# NB-Fi-Router.net
KiCad netlist of a schematic drawn in Altium Designer
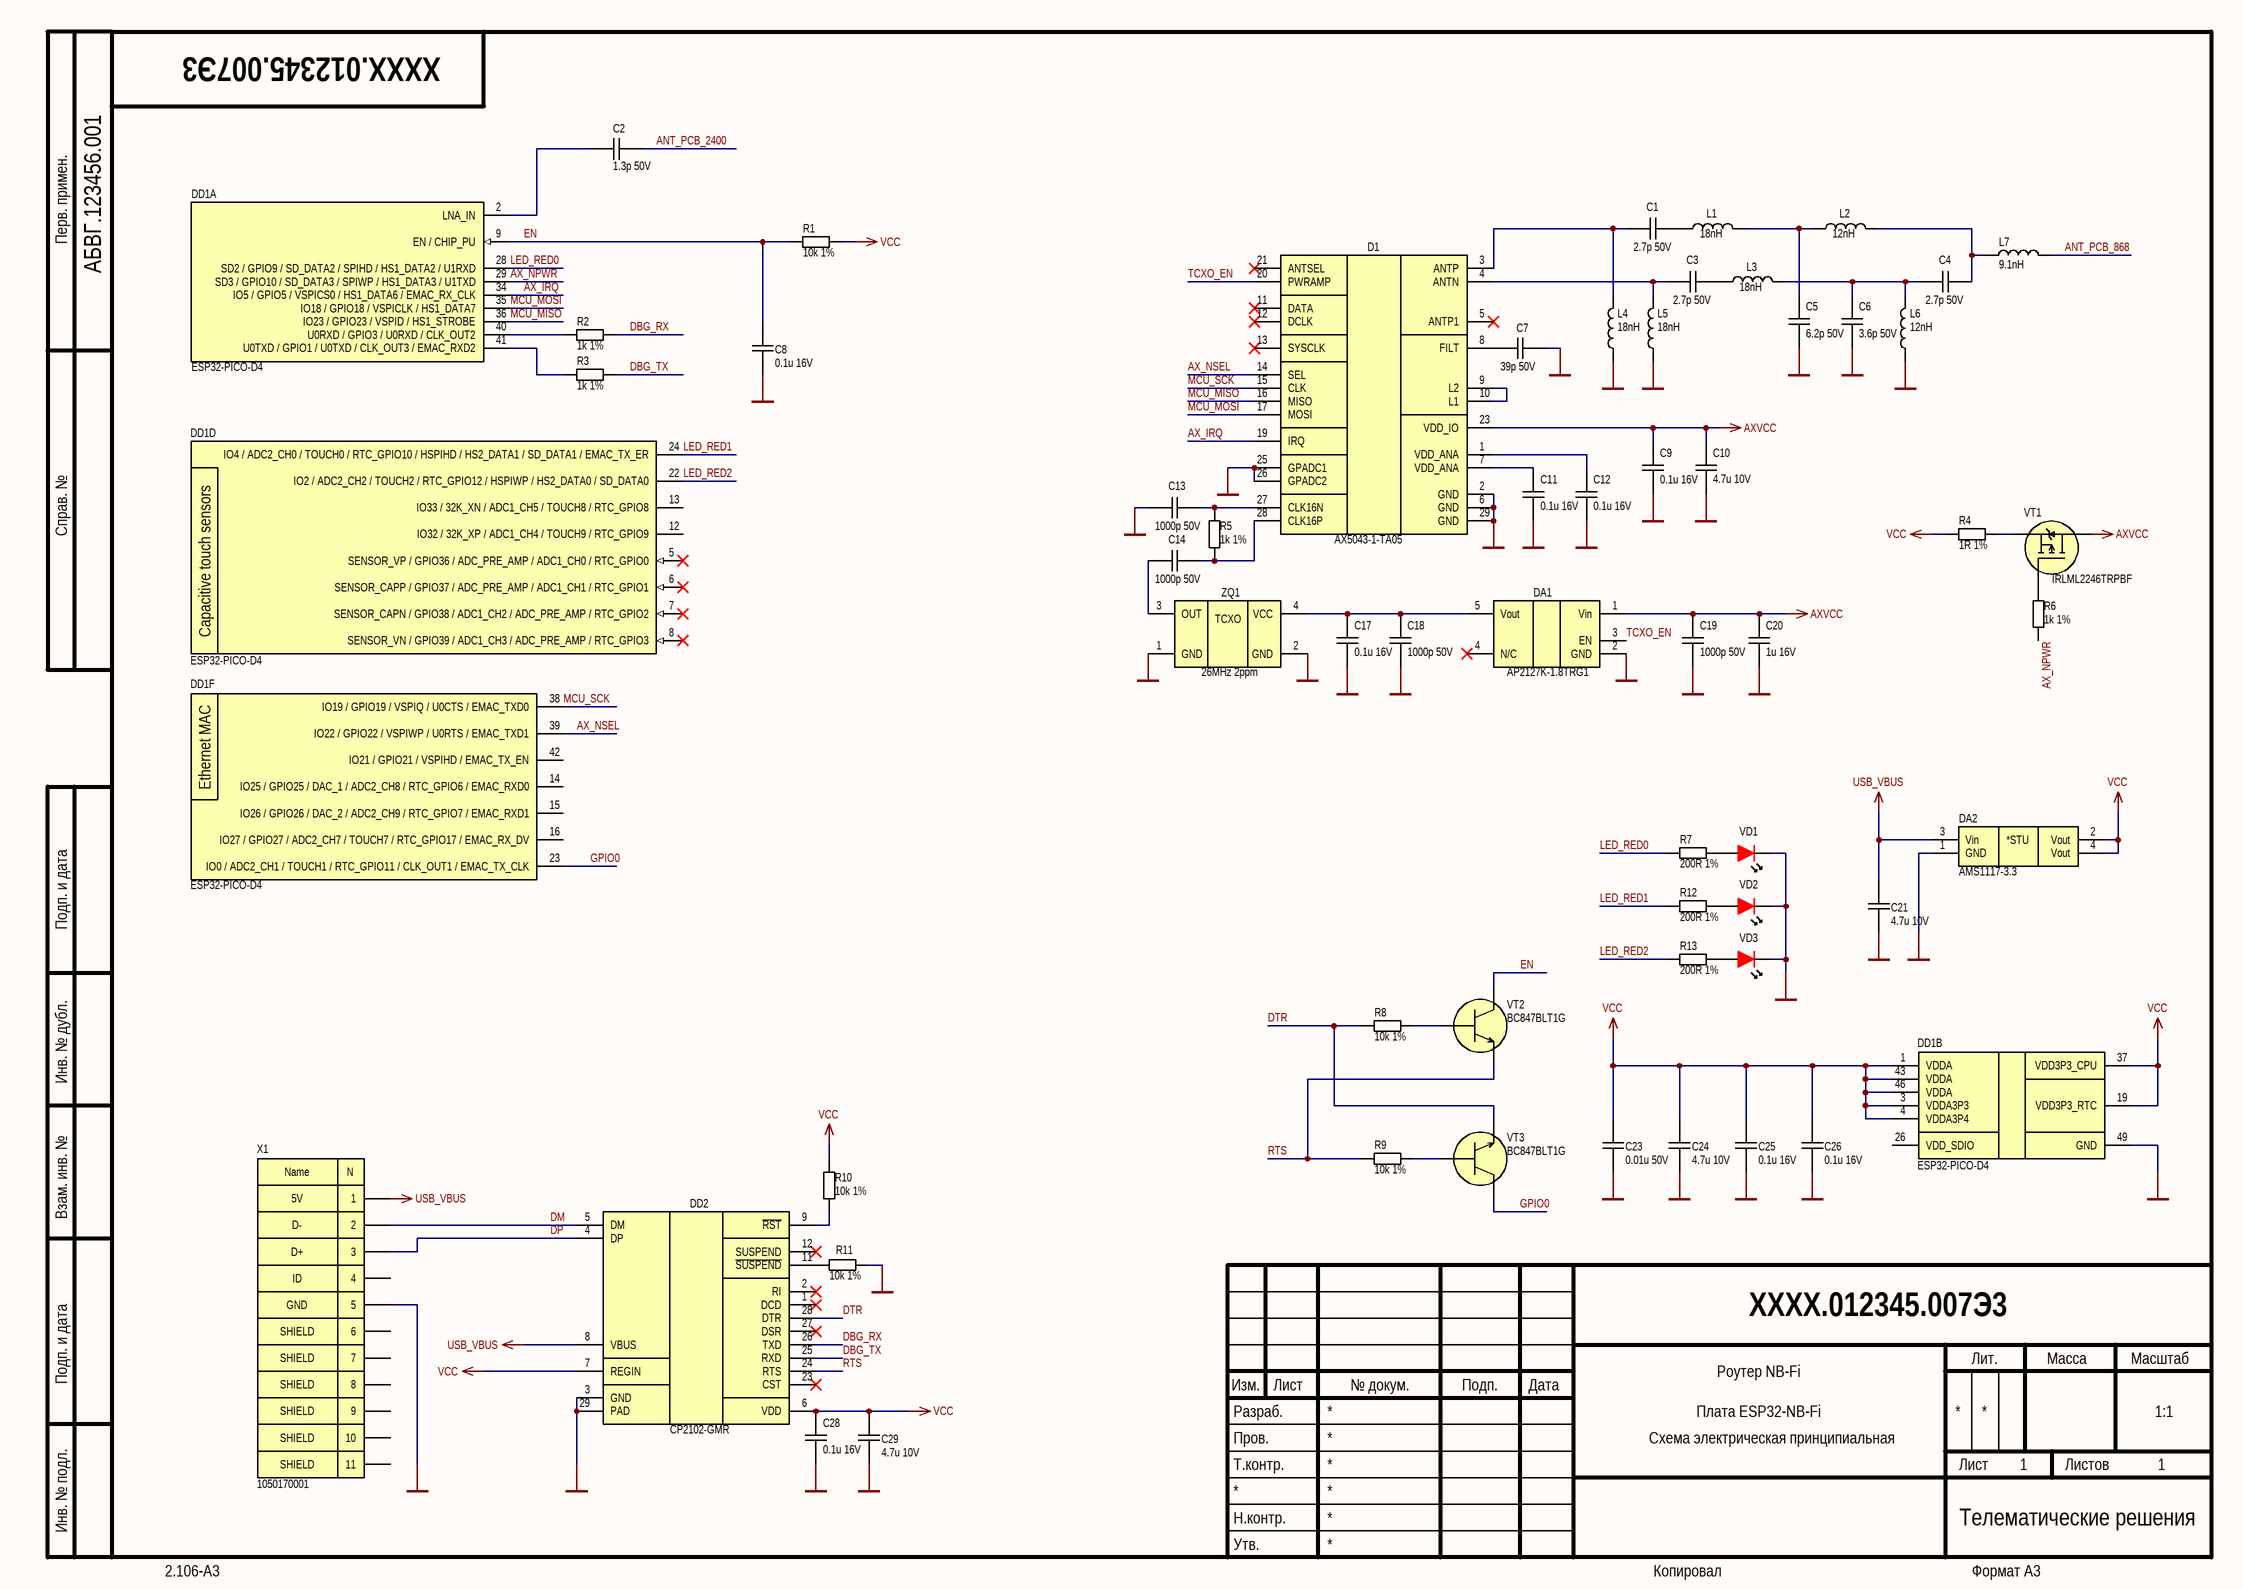
[diagram p0: NB-Fi-Router.SchDoc]

(export (version "E")
  (design (tool "Eeschema 10.0.6"))
  (components
    (comp (ref "C1")
      (value "2.7p 50V")
      (footprint "C0603")
      (description "CERCAP 2.7p/50V 0603 BNPO")
      (fields (field (name "PARTNUMBER") "CC0603BRNPO9BN2R7"))
      (libsource (lib "Capacitors") (part "CC0603BRNPO9BN2R7"))
    )
    (comp (ref "C2")
      (value "1.3p 50V")
      (footprint "C0603")
      (description "CAP CER 1.3PF 50V NPO 0603")
      (fields (field (name "PARTNUMBER") "CC0603BRNPO9BN1R3"))
      (libsource (lib "Capacitors") (part "CC0603BRNPO9BN1R3"))
    )
    (comp (ref "C3")
      (value "2.7p 50V")
      (footprint "C0603")
      (description "CERCAP 2.7p/50V 0603 BNPO")
      (fields (field (name "PARTNUMBER") "CC0603BRNPO9BN2R7"))
      (libsource (lib "Capacitors") (part "CC0603BRNPO9BN2R7"))
    )
    (comp (ref "C4")
      (value "2.7p 50V")
      (footprint "C0603")
      (description "CERCAP 2.7p/50V 0603 BNPO")
      (fields (field (name "PARTNUMBER") "CC0603BRNPO9BN2R7"))
      (libsource (lib "Capacitors") (part "CC0603BRNPO9BN2R7"))
    )
    (comp (ref "C5")
      (value "6.2p 50V")
      (footprint "C0603")
      (description "CERCAP 6.2p/50V 0603 BNPO")
      (fields (field (name "PARTNUMBER") "CC0603BRNPO9BN6R2"))
      (libsource (lib "Capacitors") (part "CC0603BRNPO9BN6R2"))
    )
    (comp (ref "C6")
      (value "3.6p 50V")
      (footprint "C0603")
      (description "CERCAP 3.6p/50V 0603 BNPO")
      (fields (field (name "PARTNUMBER") "CC0603BRNPO9BN3R6"))
      (libsource (lib "Capacitors") (part "CC0603BRNPO9BN3R6"))
    )
    (comp (ref "C7")
      (value "39p 50V")
      (footprint "C0603")
      (description "CERCAP 39p/50V 0603 JNPO")
      (fields (field (name "PARTNUMBER") "CC0603JRNPO9BN390"))
      (libsource (lib "Capacitors") (part "CC0603JRNPO9BN390"))
    )
    (comp (ref "C8")
      (value "0.1u 16V")
      (footprint "C0603")
      (description "CERCAP 0.1/16V 0603 KX7R")
      (fields (field (name "PARTNUMBER") "CC0603KRX7R7BB104"))
      (libsource (lib "Capacitors") (part "CC0603KRX7R7BB104"))
    )
    (comp (ref "C9")
      (value "0.1u 16V")
      (footprint "C0603")
      (description "CERCAP 0.1/16V 0603 KX7R")
      (fields (field (name "PARTNUMBER") "CC0603KRX7R7BB104"))
      (libsource (lib "Capacitors") (part "CC0603KRX7R7BB104"))
    )
    (comp (ref "C10")
      (value "4.7u 10V")
      (footprint "C0603")
      (description "CERCAP 4.7/10V 0603 KX5R")
      (fields (field (name "PARTNUMBER") "CC0603KRX5R6BB475"))
      (libsource (lib "Passive") (part "C"))
    )
    (comp (ref "C11")
      (value "0.1u 16V")
      (footprint "C0603")
      (description "CERCAP 0.1/16V 0603 KX7R")
      (fields (field (name "PARTNUMBER") "CC0603KRX7R7BB104"))
      (libsource (lib "Capacitors") (part "CC0603KRX7R7BB104"))
    )
    (comp (ref "C12")
      (value "0.1u 16V")
      (footprint "C0603")
      (description "CERCAP 0.1/16V 0603 KX7R")
      (fields (field (name "PARTNUMBER") "CC0603KRX7R7BB104"))
      (libsource (lib "Capacitors") (part "CC0603KRX7R7BB104"))
    )
    (comp (ref "C13")
      (value "1000p 50V")
      (footprint "C0603")
      (description "CERCAP 1000p/50V 0603 JNPO")
      (fields (field (name "PARTNUMBER") "CC0603JRNPO9BN102"))
      (libsource (lib "Capacitors") (part "CC0603JRNPO9BN102"))
    )
    (comp (ref "C14")
      (value "1000p 50V")
      (footprint "C0603")
      (description "CERCAP 1000p/50V 0603 JNPO")
      (fields (field (name "PARTNUMBER") "CC0603JRNPO9BN102"))
      (libsource (lib "Capacitors") (part "CC0603JRNPO9BN102"))
    )
    (comp (ref "C17")
      (value "0.1u 16V")
      (footprint "C0603")
      (description "CERCAP 0.1/16V 0603 KX7R")
      (fields (field (name "PARTNUMBER") "CC0603KRX7R7BB104"))
      (libsource (lib "Capacitors") (part "CC0603KRX7R7BB104"))
    )
    (comp (ref "C18")
      (value "1000p 50V")
      (footprint "C0603")
      (description "CERCAP 1000p/50V 0603 JNPO")
      (fields (field (name "PARTNUMBER") "CC0603JRNPO9BN102"))
      (libsource (lib "Capacitors") (part "CC0603JRNPO9BN102"))
    )
    (comp (ref "C19")
      (value "1000p 50V")
      (footprint "C0603")
      (description "CERCAP 1000p/50V 0603 JNPO")
      (fields (field (name "PARTNUMBER") "CC0603JRNPO9BN102"))
      (libsource (lib "Capacitors") (part "CC0603JRNPO9BN102"))
    )
    (comp (ref "C20")
      (value "1u 16V")
      (footprint "C0603")
      (description "CERCAP 1/16V 0603 KX7R")
      (fields (field (name "PARTNUMBER") "CC0603KRX7R7BB105"))
      (libsource (lib "Capacitors") (part "CC0603KRX7R7BB105"))
    )
    (comp (ref "C21")
      (value "4.7u 10V")
      (footprint "C0603")
      (description "CERCAP 4.7/10V 0603 KX5R")
      (fields (field (name "PARTNUMBER") "CC0603KRX5R6BB475"))
      (libsource (lib "Capacitors") (part "CC0603KRX5R6BB475"))
    )
    (comp (ref "C23")
      (value "0.01u 50V")
      (footprint "C0603")
      (description "CAP CER 10000PF 50V X7R 0603")
      (fields (field (name "PARTNUMBER") "CC0603KRX7R9BB103"))
      (libsource (lib "Capacitors") (part "CC0603KRX7R9BB103"))
    )
    (comp (ref "C24")
      (value "4.7u 10V")
      (footprint "C0603")
      (description "CERCAP 4.7/10V 0603 KX5R")
      (fields (field (name "PARTNUMBER") "CC0603KRX5R6BB475"))
      (libsource (lib "Passive") (part "C"))
    )
    (comp (ref "C25")
      (value "0.1u 16V")
      (footprint "C0603")
      (description "CERCAP 0.1/16V 0603 KX7R")
      (fields (field (name "PARTNUMBER") "CC0603KRX7R7BB104"))
      (libsource (lib "Capacitors") (part "CC0603KRX7R7BB104"))
    )
    (comp (ref "C26")
      (value "0.1u 16V")
      (footprint "C0603")
      (description "CERCAP 0.1/16V 0603 KX7R")
      (fields (field (name "PARTNUMBER") "CC0603KRX7R7BB104"))
      (libsource (lib "Capacitors") (part "CC0603KRX7R7BB104"))
    )
    (comp (ref "C28")
      (value "0.1u 16V")
      (footprint "C0603")
      (description "CERCAP 0.1/16V 0603 KX7R")
      (fields (field (name "PARTNUMBER") "CC0603KRX7R7BB104"))
      (libsource (lib "Capacitors") (part "CC0603KRX7R7BB104"))
    )
    (comp (ref "C29")
      (value "4.7u 10V")
      (footprint "C0603")
      (description "CERCAP 4.7/10V 0603 KX5R")
      (fields (field (name "PARTNUMBER") "CC0603KRX5R6BB475"))
      (libsource (lib "Capacitors") (part "CC0603KRX5R6BB475"))
    )
    (comp (ref "D1")
      (value "AX5043-1-TA05")
      (footprint "QFN28")
      (description "RF Transceiver RADIO TRANSCEIVER")
      (libsource (lib "Integrated Circuits (ICs)") (part "AX5043-1-TA05"))
    )
    (comp (ref "DA1")
      (value "AP2127K-1.8TRG1")
      (footprint "SOT23-5")
      (description "LDO Voltage Regulators 1.8V 80mA CMOS LDO w/Enable")
      (libsource (lib "Integrated Circuits (ICs)") (part "AP2127K-1.8TRG1"))
    )
    (comp (ref "DA2")
      (value "AMS1117-3.3")
      (footprint "SOT223-4")
      (description "1A LOW DROPOUT VOLTAGE REGULATOR")
      (libsource (lib "Integrated Circuits (ICs)") (part "AMS1117-3.3"))
    )
    (comp (ref "DD1")
      (value "ESP32-PICO-D4")
      (footprint "QFN48-7x7")
      (libsource (lib "Integrated Circuits (ICs)") (part "ESP32-PICO-D4"))
    )
    (comp (ref "DD2")
      (value "CP2102-GMR")
      (footprint "QFN28")
      (description "IC USB-TO-UART BRIDGE 28VQFN")
      (libsource (lib "Integrated Circuits (ICs)") (part "CP2102-GMR"))
    )
    (comp (ref "L1")
      (value "18nH")
      (footprint "L0603_LQW")
      (description "Fixed Inductors 0603 18nH 2%")
      (fields (field (name "PARTNUMBER") "LQW18AN18NG00D"))
      (libsource (lib "Inductors") (part "LQW18AN18NG00D"))
    )
    (comp (ref "L2")
      (value "12nH")
      (footprint "L0603_LQW")
      (description "Fixed Inductors 12 NH 5% (R)")
      (fields (field (name "PARTNUMBER") "LQW18AN12NJ00D"))
      (libsource (lib "Inductors") (part "LQW18AN12NJ00D"))
    )
    (comp (ref "L3")
      (value "18nH")
      (footprint "L0603_LQW")
      (description "Fixed Inductors 0603 18nH 2%")
      (fields (field (name "PARTNUMBER") "LQW18AN18NG00D"))
      (libsource (lib "Inductors") (part "LQW18AN18NG00D"))
    )
    (comp (ref "L4")
      (value "18nH")
      (footprint "L0603_LQW")
      (description "Fixed Inductors 0603 18nH 2%")
      (fields (field (name "PARTNUMBER") "LQW18AN18NG00D"))
      (libsource (lib "Inductors") (part "LQW18AN18NG00D"))
    )
    (comp (ref "L5")
      (value "18nH")
      (footprint "L0603_LQW")
      (description "Fixed Inductors 0603 18nH 2%")
      (fields (field (name "PARTNUMBER") "LQW18AN18NG00D"))
      (libsource (lib "Inductors") (part "LQW18AN18NG00D"))
    )
    (comp (ref "L6")
      (value "12nH")
      (footprint "L0603_LQW")
      (description "Fixed Inductors 12 NH 5% (R)")
      (fields (field (name "PARTNUMBER") "LQW18AN12NJ00D"))
      (libsource (lib "Inductors") (part "LQW18AN12NJ00D"))
    )
    (comp (ref "L7")
      (value "9.1nH")
      (footprint "L0603_LQW")
      (description "9.1nH Unshielded Wirewound Inductor 650mA 110mOhm Max 0603 (1608 Metric)")
      (fields (field (name "PARTNUMBER") "LQW18AN9N1D00D"))
      (libsource (lib "Inductors, Coils, Chokes") (part "LQW18AN9N1D00D"))
    )
    (comp (ref "R1")
      (value "10k 1%")
      (footprint "R0603")
      (description "RES 0603 10K 1%")
      (fields (field (name "PARTNUMBER") "RC0603FR-0710KL"))
      (libsource (lib "Resistors") (part "RC0603FR-0710KL"))
    )
    (comp (ref "R2")
      (value "1k 1%")
      (footprint "R0603")
      (description "RES 0603 1K 1%")
      (fields (field (name "PARTNUMBER") "RC0603FR-071KL"))
      (libsource (lib "Resistors") (part "RC0603FR-071KL"))
    )
    (comp (ref "R3")
      (value "1k 1%")
      (footprint "R0603")
      (description "RES 0603 1K 1%")
      (fields (field (name "PARTNUMBER") "RC0603FR-071KL"))
      (libsource (lib "Resistors") (part "RC0603FR-071KL"))
    )
    (comp (ref "R4")
      (value "1R 1%")
      (footprint "R0603")
      (description "RES 0603 1R 1%")
      (fields (field (name "PARTNUMBER") "RC0603FR-071RL"))
      (libsource (lib "Passive") (part "R"))
    )
    (comp (ref "R5")
      (value "1k 1%")
      (footprint "R0603")
      (description "RES 0603 1K 1%")
      (fields (field (name "PARTNUMBER") "RC0603FR-071KL"))
      (libsource (lib "Resistors") (part "RC0603FR-071KL"))
    )
    (comp (ref "R6")
      (value "1k 1%")
      (footprint "R0603")
      (description "RES 0603 1K 1%")
      (fields (field (name "PARTNUMBER") "RC0603FR-071KL"))
      (libsource (lib "Resistors") (part "RC0603FR-071KL"))
    )
    (comp (ref "R7")
      (value "200R 1%")
      (footprint "R0603")
      (description "RES 0603 200R 1%")
      (fields (field (name "PARTNUMBER") "RC0603FR-07200RL"))
      (libsource (lib "Resistors") (part "RC0603FR-07200RL"))
    )
    (comp (ref "R8")
      (value "10k 1%")
      (footprint "R0603")
      (description "RES 0603 10K 1%")
      (fields (field (name "PARTNUMBER") "RC0603FR-0710KL"))
      (libsource (lib "Resistors") (part "RC0603FR-0710KL"))
    )
    (comp (ref "R9")
      (value "10k 1%")
      (footprint "R0603")
      (description "RES 0603 10K 1%")
      (fields (field (name "PARTNUMBER") "RC0603FR-0710KL"))
      (libsource (lib "Resistors") (part "RC0603FR-0710KL"))
    )
    (comp (ref "R10")
      (value "10k 1%")
      (footprint "R0603")
      (description "RES 0603 10K 1%")
      (fields (field (name "PARTNUMBER") "RC0603FR-0710KL"))
      (libsource (lib "") (part "RC0603FR-0710KL_2"))
    )
    (comp (ref "R11")
      (value "10k 1%")
      (footprint "R0603")
      (description "RES 0603 10K 1%")
      (fields (field (name "PARTNUMBER") "RC0603FR-0710KL"))
      (libsource (lib "") (part "RC0603FR-0710KL_1"))
    )
    (comp (ref "R12")
      (value "200R 1%")
      (footprint "R0603")
      (description "RES 0603 200R 1%")
      (fields (field (name "PARTNUMBER") "RC0603FR-07200RL"))
      (libsource (lib "Resistors") (part "RC0603FR-07200RL"))
    )
    (comp (ref "R13")
      (value "200R 1%")
      (footprint "R0603")
      (description "RES 0603 200R 1%")
      (fields (field (name "PARTNUMBER") "RC0603FR-07200RL"))
      (libsource (lib "Resistors") (part "RC0603FR-07200RL"))
    )
    (comp (ref "VD1")
      (value "RED")
      (footprint "LED0603_RED")
      (description "LED Red 0603")
      (fields (field (name "PARTNUMBER") "FYLS-0603URC"))
      (libsource (lib "Diodes") (part "FYLS-0603URC"))
    )
    (comp (ref "VD2")
      (value "RED")
      (footprint "LED0603_RED")
      (description "LED Red 0603")
      (fields (field (name "PARTNUMBER") "FYLS-0603URC"))
      (libsource (lib "Diodes") (part "FYLS-0603URC"))
    )
    (comp (ref "VD3")
      (value "RED")
      (footprint "LED0603_RED")
      (description "LED Red 0603")
      (fields (field (name "PARTNUMBER") "FYLS-0603URC"))
      (libsource (lib "Diodes") (part "FYLS-0603URC"))
    )
    (comp (ref "VT1")
      (value "IRLML2246TRPBF")
      (footprint "SOT23-3L")
      (description "MOSFET MOSFT PCh -20V -2.6A 135mOhm -2.5V cpbl")
      (libsource (lib "Discrete Semiconductor Products") (part "IRLML2246TRPBF"))
    )
    (comp (ref "VT2")
      (value "BC847BLT1G")
      (footprint "SOT23-3L")
      (description "Bipolar (BJT) Transistor NPN 45V 100mA 100MHz 300mW Surface Mount SOT-23-3 (TO-236)")
      (libsource (lib "Discrete Semiconductor Products") (part "BC847BLT1G"))
    )
    (comp (ref "VT3")
      (value "BC847BLT1G")
      (footprint "SOT23-3L")
      (description "Bipolar (BJT) Transistor NPN 45V 100mA 100MHz 300mW Surface Mount SOT-23-3 (TO-236)")
      (libsource (lib "Discrete Semiconductor Products") (part "BC847BLT1G"))
    )
    (comp (ref "X1")
      (value "1050170001")
      (footprint "1050170001")
      (description "USB - micro B USB 2.0 Receptacle Connector 5 Position Surface Mount, Right Angle; Through Hole")
      (libsource (lib "Connectors") (part "1050170001"))
    )
    (comp (ref "ZQ1")
      (value "26MHz 2ppm")
      (footprint "QSMD2.0x1.6x0.7")
      (description "TCXO Oscillator 4-pin")
      (fields (field (name "PARTNUMBER") "NT2016SA-26.000000MHZ-NBG2"))
      (libsource (lib "Crystals, Oscillators, Resonators") (part "NT2016SA-26.000000MHZ-NBG2"))
    )
  )
  (nets
    (net (code "1") (name "/ANT_PCB_868") (class "Default")
      (node (ref "L7") (pin "2") (pinfunction "2_2") (pintype "passive"))
    )
    (net (code "2") (name "/ANT_PCB_2400") (class "Default")
      (node (ref "C2") (pin "2") (pinfunction "2_2") (pintype "passive"))
    )
    (net (code "3") (name "/AX_IRQ") (class "Default")
      (node (ref "D1") (pin "19") (pinfunction "IRQ_19") (pintype "passive"))
      (node (ref "DD1") (pin "34") (pinfunction "IO5_/_GPIO5_/_VSPICS0_/_HS1_DATA6_/_EMAC_RX_CLK_34") (pintype "passive"))
    )
    (net (code "4") (name "/AX_NPWR") (class "Default")
      (node (ref "DD1") (pin "29") (pinfunction "SD3_/_GPIO10_/_SD_DATA3_/_SPIWP_/_HS1_DATA3_/_U1TXD_29") (pintype "open_collector"))
      (node (ref "R6") (pin "1") (pinfunction "1_1") (pintype "passive"))
    )
    (net (code "5") (name "/AX_NSEL") (class "Default")
      (node (ref "D1") (pin "14") (pinfunction "SEL_14") (pintype "passive"))
      (node (ref "DD1") (pin "39") (pinfunction "IO22_/_GPIO22_/_VSPIWP_/_U0RTS_/_EMAC_TXD1_39") (pintype "passive"))
    )
    (net (code "6") (name "/DBG_RX") (class "Default")
      (node (ref "DD2") (pin "26") (pinfunction "TXD_26") (pintype "passive"))
      (node (ref "R2") (pin "2") (pinfunction "2_2") (pintype "passive"))
    )
    (net (code "7") (name "/DBG_TX") (class "Default")
      (node (ref "DD2") (pin "25") (pinfunction "RXD_25") (pintype "passive"))
      (node (ref "R3") (pin "2") (pinfunction "2_2") (pintype "passive"))
    )
    (net (code "8") (name "/DM") (class "Default")
      (node (ref "DD2") (pin "5") (pinfunction "DM_5") (pintype "passive"))
      (node (ref "X1") (pin "2") (pinfunction "2_2") (pintype "passive"))
    )
    (net (code "9") (name "/DP") (class "Default")
      (node (ref "DD2") (pin "4") (pinfunction "DP_4") (pintype "passive"))
      (node (ref "X1") (pin "3") (pinfunction "3_3") (pintype "passive"))
    )
    (net (code "10") (name "/DTR") (class "Default")
      (node (ref "DD2") (pin "28") (pinfunction "DTR_28") (pintype "passive"))
      (node (ref "R8") (pin "1") (pinfunction "1_1") (pintype "passive"))
      (node (ref "VT3") (pin "2") (pinfunction "E_2") (pintype "passive"))
    )
    (net (code "11") (name "/EN") (class "Default")
      (node (ref "C8") (pin "2") (pinfunction "2_2") (pintype "passive"))
      (node (ref "DD1") (pin "9") (pinfunction "EN_/_CHIP_PU_9") (pintype "input"))
      (node (ref "R1") (pin "1") (pinfunction "1_1") (pintype "passive"))
      (node (ref "VT2") (pin "3") (pinfunction "C_3") (pintype "passive"))
    )
    (net (code "12") (name "/GPIO0") (class "Default")
      (node (ref "DD1") (pin "23") (pinfunction "IO0_/_ADC2_CH1_/_TOUCH1_/_RTC_GPIO11_/_CLK_OUT1_/_EMAC_TX_CLK_23") (pintype "passive"))
      (node (ref "VT3") (pin "3") (pinfunction "C_3") (pintype "passive"))
    )
    (net (code "13") (name "/LED_RED0") (class "Default")
      (node (ref "DD1") (pin "28") (pinfunction "SD2_/_GPIO9_/_SD_DATA2_/_SPIHD_/_HS1_DATA2_/_U1RXD_28") (pintype "passive"))
      (node (ref "R7") (pin "1") (pinfunction "1_1") (pintype "passive"))
    )
    (net (code "14") (name "/LED_RED1") (class "Default")
      (node (ref "DD1") (pin "24") (pinfunction "IO4_/_ADC2_CH0_/_TOUCH0_/_RTC_GPIO10_/_HSPIHD_/_HS2_DATA1_/_SD_DATA1_/_EMAC_TX_ER_24") (pintype "passive"))
      (node (ref "R12") (pin "1") (pinfunction "1_1") (pintype "passive"))
    )
    (net (code "15") (name "/LED_RED2") (class "Default")
      (node (ref "DD1") (pin "22") (pinfunction "IO2_/_ADC2_CH2_/_TOUCH2_/_RTC_GPIO12_/_HSPIWP_/_HS2_DATA0_/_SD_DATA0_22") (pintype "open_collector"))
      (node (ref "R13") (pin "1") (pinfunction "1_1") (pintype "passive"))
    )
    (net (code "16") (name "/MCU_MISO") (class "Default")
      (node (ref "D1") (pin "16") (pinfunction "MISO_16") (pintype "passive"))
      (node (ref "DD1") (pin "36") (pinfunction "IO23_/_GPIO23_/_VSPID_/_HS1_STROBE_36") (pintype "passive"))
    )
    (net (code "17") (name "/MCU_MOSI") (class "Default")
      (node (ref "D1") (pin "17") (pinfunction "MOSI_17") (pintype "passive"))
      (node (ref "DD1") (pin "35") (pinfunction "IO18_/_GPIO18_/_VSPICLK_/_HS1_DATA7_35") (pintype "open_collector"))
    )
    (net (code "18") (name "/MCU_SCK") (class "Default")
      (node (ref "D1") (pin "15") (pinfunction "CLK_15") (pintype "passive"))
      (node (ref "DD1") (pin "38") (pinfunction "IO19_/_GPIO19_/_VSPIQ_/_U0CTS_/_EMAC_TXD0_38") (pintype "passive"))
    )
    (net (code "19") (name "/RTS") (class "Default")
      (node (ref "DD2") (pin "24") (pinfunction "RTS_24") (pintype "passive"))
      (node (ref "R9") (pin "1") (pinfunction "1_1") (pintype "passive"))
      (node (ref "VT2") (pin "2") (pinfunction "E_2") (pintype "passive"))
    )
    (net (code "20") (name "/TCXO_EN") (class "Default")
      (node (ref "D1") (pin "20") (pinfunction "PWRAMP_20") (pintype "passive"))
      (node (ref "DA1") (pin "3") (pinfunction "EN_3") (pintype "passive"))
    )
    (net (code "21") (name "AXVCC") (class "Default")
      (node (ref "C10") (pin "2") (pinfunction "2_2") (pintype "passive"))
      (node (ref "C19") (pin "1") (pinfunction "1_1") (pintype "passive"))
      (node (ref "C20") (pin "2") (pinfunction "2_2") (pintype "passive"))
      (node (ref "C9") (pin "2") (pinfunction "2_2") (pintype "passive"))
      (node (ref "D1") (pin "23") (pinfunction "VDD_IO_23") (pintype "passive"))
      (node (ref "DA1") (pin "1") (pinfunction "Vin_1") (pintype "passive"))
      (node (ref "VT1") (pin "3") (pinfunction "D_3") (pintype "passive"))
    )
    (net (code "22") (name "GND") (class "Default")
      (node (ref "C10") (pin "1") (pinfunction "1_1") (pintype "passive"))
      (node (ref "C11") (pin "1") (pinfunction "1_1") (pintype "passive"))
      (node (ref "C12") (pin "1") (pinfunction "1_1") (pintype "passive"))
      (node (ref "C13") (pin "2") (pinfunction "2_2") (pintype "passive"))
      (node (ref "C17") (pin "1") (pinfunction "1_1") (pintype "passive"))
      (node (ref "C18") (pin "2") (pinfunction "2_2") (pintype "passive"))
      (node (ref "C19") (pin "2") (pinfunction "2_2") (pintype "passive"))
      (node (ref "C20") (pin "1") (pinfunction "1_1") (pintype "passive"))
      (node (ref "C21") (pin "1") (pinfunction "1_1") (pintype "passive"))
      (node (ref "C23") (pin "1") (pinfunction "1_1") (pintype "passive"))
      (node (ref "C24") (pin "1") (pinfunction "1_1") (pintype "passive"))
      (node (ref "C25") (pin "1") (pinfunction "1_1") (pintype "passive"))
      (node (ref "C26") (pin "1") (pinfunction "1_1") (pintype "passive"))
      (node (ref "C28") (pin "1") (pinfunction "1_1") (pintype "passive"))
      (node (ref "C29") (pin "1") (pinfunction "1_1") (pintype "passive"))
      (node (ref "C5") (pin "1") (pinfunction "1_1") (pintype "passive"))
      (node (ref "C6") (pin "1") (pinfunction "1_1") (pintype "passive"))
      (node (ref "C7") (pin "2") (pinfunction "2_2") (pintype "passive"))
      (node (ref "C8") (pin "1") (pinfunction "1_1") (pintype "passive"))
      (node (ref "C9") (pin "1") (pinfunction "1_1") (pintype "passive"))
      (node (ref "D1") (pin "2") (pinfunction "GND_2") (pintype "passive"))
      (node (ref "D1") (pin "25") (pinfunction "GPADC1_25") (pintype "passive"))
      (node (ref "D1") (pin "26") (pinfunction "GPADC2_26") (pintype "passive"))
      (node (ref "D1") (pin "29") (pinfunction "GND_29") (pintype "passive"))
      (node (ref "D1") (pin "6") (pinfunction "GND_6") (pintype "passive"))
      (node (ref "DA1") (pin "2") (pinfunction "GND_2") (pintype "passive"))
      (node (ref "DA2") (pin "1") (pinfunction "GND_1") (pintype "passive"))
      (node (ref "DD1") (pin "49") (pinfunction "GND_49") (pintype "power_in"))
      (node (ref "DD2") (pin "29") (pinfunction "PAD_29") (pintype "passive"))
      (node (ref "DD2") (pin "3") (pinfunction "GND_3") (pintype "passive"))
      (node (ref "L4") (pin "1") (pinfunction "1_1") (pintype "passive"))
      (node (ref "L5") (pin "1") (pinfunction "1_1") (pintype "passive"))
      (node (ref "L6") (pin "1") (pinfunction "1_1") (pintype "passive"))
      (node (ref "R11") (pin "1") (pinfunction "1_1") (pintype "passive"))
      (node (ref "VD1") (pin "2") (pinfunction "2_2") (pintype "passive"))
      (node (ref "VD2") (pin "2") (pinfunction "2_2") (pintype "passive"))
      (node (ref "VD3") (pin "2") (pinfunction "2_2") (pintype "passive"))
      (node (ref "X1") (pin "5") (pinfunction "5_5") (pintype "passive"))
      (node (ref "ZQ1") (pin "1") (pinfunction "GND_1") (pintype "passive"))
      (node (ref "ZQ1") (pin "2") (pinfunction "GND_2") (pintype "passive"))
    )
    (net (code "23") (name "Net-(C1-Pad2)") (class "Default")
      (node (ref "C1") (pin "2") (pinfunction "2_2") (pintype "passive"))
      (node (ref "L1") (pin "1") (pinfunction "1_1") (pintype "passive"))
    )
    (net (code "24") (name "Net-(C3-Pad2)") (class "Default")
      (node (ref "C3") (pin "2") (pinfunction "2_2") (pintype "passive"))
      (node (ref "L3") (pin "1") (pinfunction "1_1") (pintype "passive"))
    )
    (net (code "25") (name "Net-(C4-Pad1)") (class "Default")
      (node (ref "C4") (pin "1") (pinfunction "1_1") (pintype "passive"))
      (node (ref "C6") (pin "2") (pinfunction "2_2") (pintype "passive"))
      (node (ref "L3") (pin "2") (pinfunction "2_2") (pintype "passive"))
      (node (ref "L6") (pin "2") (pinfunction "2_2") (pintype "passive"))
    )
    (net (code "26") (name "Net-(C4-Pad2)") (class "Default")
      (node (ref "C4") (pin "2") (pinfunction "2_2") (pintype "passive"))
      (node (ref "L2") (pin "2") (pinfunction "2_2") (pintype "passive"))
      (node (ref "L7") (pin "1") (pinfunction "1_1") (pintype "passive"))
    )
    (net (code "27") (name "Net-(C5-Pad2)") (class "Default")
      (node (ref "C5") (pin "2") (pinfunction "2_2") (pintype "passive"))
      (node (ref "L1") (pin "2") (pinfunction "2_2") (pintype "passive"))
      (node (ref "L2") (pin "1") (pinfunction "1_1") (pintype "passive"))
    )
    (net (code "28") (name "Net-(C11-Pad2)") (class "Default")
      (node (ref "C11") (pin "2") (pinfunction "2_2") (pintype "passive"))
      (node (ref "D1") (pin "7") (pinfunction "VDD_ANA_7") (pintype "passive"))
    )
    (net (code "29") (name "Net-(C12-Pad2)") (class "Default")
      (node (ref "C12") (pin "2") (pinfunction "2_2") (pintype "passive"))
      (node (ref "D1") (pin "1") (pinfunction "VDD_ANA_1") (pintype "passive"))
    )
    (net (code "30") (name "Net-(D1-ANTN)") (class "Default")
      (node (ref "C3") (pin "1") (pinfunction "1_1") (pintype "passive"))
      (node (ref "D1") (pin "4") (pinfunction "ANTN_4") (pintype "passive"))
      (node (ref "L5") (pin "2") (pinfunction "2_2") (pintype "passive"))
    )
    (net (code "31") (name "Net-(D1-ANTP)") (class "Default")
      (node (ref "C1") (pin "1") (pinfunction "1_1") (pintype "passive"))
      (node (ref "D1") (pin "3") (pinfunction "ANTP_3") (pintype "passive"))
      (node (ref "L4") (pin "2") (pinfunction "2_2") (pintype "passive"))
    )
    (net (code "32") (name "Net-(D1-CLK16N)") (class "Default")
      (node (ref "C13") (pin "1") (pinfunction "1_1") (pintype "passive"))
      (node (ref "D1") (pin "27") (pinfunction "CLK16N_27") (pintype "passive"))
      (node (ref "R5") (pin "2") (pinfunction "2_2") (pintype "passive"))
    )
    (net (code "33") (name "Net-(D1-CLK16P)") (class "Default")
      (node (ref "C14") (pin "1") (pinfunction "1_1") (pintype "passive"))
      (node (ref "D1") (pin "28") (pinfunction "CLK16P_28") (pintype "passive"))
      (node (ref "R5") (pin "1") (pinfunction "1_1") (pintype "passive"))
    )
    (net (code "34") (name "Net-(D1-FILT)") (class "Default")
      (node (ref "C7") (pin "1") (pinfunction "1_1") (pintype "passive"))
      (node (ref "D1") (pin "8") (pinfunction "FILT_8") (pintype "passive"))
    )
    (net (code "35") (name "Net-(D1-L1)") (class "Default")
      (node (ref "D1") (pin "10") (pinfunction "L1_10") (pintype "passive"))
      (node (ref "D1") (pin "9") (pinfunction "L2_9") (pintype "passive"))
    )
    (net (code "36") (name "Net-(DA1-Vout)") (class "Default")
      (node (ref "C17") (pin "2") (pinfunction "2_2") (pintype "passive"))
      (node (ref "C18") (pin "1") (pinfunction "1_1") (pintype "passive"))
      (node (ref "DA1") (pin "5") (pinfunction "Vout_5") (pintype "passive"))
      (node (ref "ZQ1") (pin "4") (pinfunction "VCC_4") (pintype "passive"))
    )
    (net (code "37") (name "Net-(DD1A-LNA_IN)") (class "Default")
      (node (ref "C2") (pin "1") (pinfunction "1_1") (pintype "passive"))
      (node (ref "DD1") (pin "2") (pinfunction "LNA_IN_2") (pintype "passive"))
    )
    (net (code "38") (name "Net-(DD1A-U0RXD_{slash}_GPIO3_{slash}_U0RXD_{slash}_CLK_OUT2)") (class "Default")
      (node (ref "DD1") (pin "40") (pinfunction "U0RXD_/_GPIO3_/_U0RXD_/_CLK_OUT2_40") (pintype "passive"))
      (node (ref "R2") (pin "1") (pinfunction "1_1") (pintype "passive"))
    )
    (net (code "39") (name "Net-(DD1A-U0TXD_{slash}_GPIO1_{slash}_U0TXD_{slash}_CLK_OUT3_{slash}_EMAC_RXD2)") (class "Default")
      (node (ref "DD1") (pin "41") (pinfunction "U0TXD_/_GPIO1_/_U0TXD_/_CLK_OUT3_/_EMAC_RXD2_41") (pintype "passive"))
      (node (ref "R3") (pin "1") (pinfunction "1_1") (pintype "passive"))
    )
    (net (code "40") (name "Net-(DD2-~{RST})") (class "Default")
      (node (ref "DD2") (pin "9") (pinfunction "~{RST}_9") (pintype "passive"))
      (node (ref "R10") (pin "1") (pinfunction "1_1") (pintype "passive"))
    )
    (net (code "41") (name "Net-(DD2-~{SUSPEND})") (class "Default")
      (node (ref "DD2") (pin "11") (pinfunction "~{SUSPEND}_11") (pintype "passive"))
      (node (ref "R11") (pin "2") (pinfunction "2_2") (pintype "passive"))
    )
    (net (code "42") (name "Net-(R7-Pad2)") (class "Default")
      (node (ref "R7") (pin "2") (pinfunction "2_2") (pintype "passive"))
      (node (ref "VD1") (pin "1") (pinfunction "1_1") (pintype "passive"))
    )
    (net (code "43") (name "Net-(R12-Pad2)") (class "Default")
      (node (ref "R12") (pin "2") (pinfunction "2_2") (pintype "passive"))
      (node (ref "VD2") (pin "1") (pinfunction "1_1") (pintype "passive"))
    )
    (net (code "44") (name "Net-(R13-Pad2)") (class "Default")
      (node (ref "R13") (pin "2") (pinfunction "2_2") (pintype "passive"))
      (node (ref "VD3") (pin "1") (pinfunction "1_1") (pintype "passive"))
    )
    (net (code "45") (name "Net-(VT1-G)") (class "Default")
      (node (ref "R6") (pin "2") (pinfunction "2_2") (pintype "passive"))
      (node (ref "VT1") (pin "1") (pinfunction "G_1") (pintype "passive"))
    )
    (net (code "46") (name "Net-(VT1-S)") (class "Default")
      (node (ref "R4") (pin "2") (pinfunction "2_2") (pintype "passive"))
      (node (ref "VT1") (pin "2") (pinfunction "S_2") (pintype "passive"))
    )
    (net (code "47") (name "Net-(VT2-B)") (class "Default")
      (node (ref "R8") (pin "2") (pinfunction "2_2") (pintype "passive"))
      (node (ref "VT2") (pin "1") (pinfunction "B_1") (pintype "passive"))
    )
    (net (code "48") (name "Net-(VT3-B)") (class "Default")
      (node (ref "R9") (pin "2") (pinfunction "2_2") (pintype "passive"))
      (node (ref "VT3") (pin "1") (pinfunction "B_1") (pintype "passive"))
    )
    (net (code "49") (name "Net-(ZQ1-OUT)") (class "Default")
      (node (ref "C14") (pin "2") (pinfunction "2_2") (pintype "passive"))
      (node (ref "ZQ1") (pin "3") (pinfunction "OUT_3") (pintype "passive"))
    )
    (net (code "50") (name "USB_VBUS") (class "Default")
      (node (ref "C21") (pin "2") (pinfunction "2_2") (pintype "passive"))
      (node (ref "DA2") (pin "3") (pinfunction "Vin_3") (pintype "passive"))
      (node (ref "DD2") (pin "8") (pinfunction "VBUS_8") (pintype "passive"))
      (node (ref "X1") (pin "1") (pinfunction "1_1") (pintype "passive"))
    )
    (net (code "51") (name "VCC") (class "Default")
      (node (ref "C23") (pin "2") (pinfunction "2_2") (pintype "passive"))
      (node (ref "C24") (pin "2") (pinfunction "2_2") (pintype "passive"))
      (node (ref "C25") (pin "2") (pinfunction "2_2") (pintype "passive"))
      (node (ref "C26") (pin "2") (pinfunction "2_2") (pintype "passive"))
      (node (ref "C28") (pin "2") (pinfunction "2_2") (pintype "passive"))
      (node (ref "C29") (pin "2") (pinfunction "2_2") (pintype "passive"))
      (node (ref "DA2") (pin "2") (pinfunction "Vout_2") (pintype "passive"))
      (node (ref "DA2") (pin "4") (pinfunction "Vout_4") (pintype "passive"))
      (node (ref "DD1") (pin "1") (pinfunction "VDDA_1") (pintype "power_in"))
      (node (ref "DD1") (pin "19") (pinfunction "VDD3P3_RTC_19") (pintype "power_in"))
      (node (ref "DD1") (pin "3") (pinfunction "VDDA3P3_3") (pintype "power_in"))
      (node (ref "DD1") (pin "37") (pinfunction "VDD3P3_CPU_37") (pintype "power_in"))
      (node (ref "DD1") (pin "4") (pinfunction "VDDA3P4_4") (pintype "power_in"))
      (node (ref "DD1") (pin "43") (pinfunction "VDDA_43") (pintype "power_in"))
      (node (ref "DD1") (pin "46") (pinfunction "VDDA_46") (pintype "power_in"))
      (node (ref "DD2") (pin "6") (pinfunction "VDD_6") (pintype "passive"))
      (node (ref "DD2") (pin "7") (pinfunction "REGIN_7") (pintype "passive"))
      (node (ref "R1") (pin "2") (pinfunction "2_2") (pintype "passive"))
      (node (ref "R10") (pin "2") (pinfunction "2_2") (pintype "passive"))
      (node (ref "R4") (pin "1") (pinfunction "1_1") (pintype "passive"))
    )
    (net (code "52") (name "unconnected-(D1-ANTP1-Pad5)") (class "Default")
      (node (ref "D1") (pin "5") (pinfunction "ANTP1_5") (pintype "passive+no_connect"))
    )
    (net (code "53") (name "unconnected-(D1-ANTSEL-Pad21)") (class "Default")
      (node (ref "D1") (pin "21") (pinfunction "ANTSEL_21") (pintype "passive+no_connect"))
    )
    (net (code "54") (name "unconnected-(D1-DATA-Pad11)") (class "Default")
      (node (ref "D1") (pin "11") (pinfunction "DATA_11") (pintype "passive+no_connect"))
    )
    (net (code "55") (name "unconnected-(D1-DCLK-Pad12)") (class "Default")
      (node (ref "D1") (pin "12") (pinfunction "DCLK_12") (pintype "passive+no_connect"))
    )
    (net (code "56") (name "unconnected-(D1-SYSCLK-Pad13)") (class "Default")
      (node (ref "D1") (pin "13") (pinfunction "SYSCLK_13") (pintype "passive+no_connect"))
    )
    (net (code "57") (name "unconnected-(DA1-N{slash}C-Pad4)") (class "Default")
      (node (ref "DA1") (pin "4") (pinfunction "N/C_4") (pintype "passive+no_connect"))
    )
    (net (code "58") (name "unconnected-(DD1B-VDD_SDIO-Pad26)") (class "Default")
      (node (ref "DD1") (pin "26") (pinfunction "VDD_SDIO_26") (pintype "power_in"))
    )
    (net (code "59") (name "unconnected-(DD1D-IO32_{slash}_32K_XP_{slash}_ADC1_CH4_{slash}_TOUCH9_{slash}_RTC_GPIO9-Pad12)") (class "Default")
      (node (ref "DD1") (pin "12") (pinfunction "IO32_/_32K_XP_/_ADC1_CH4_/_TOUCH9_/_RTC_GPIO9_12") (pintype "passive"))
    )
    (net (code "60") (name "unconnected-(DD1D-IO33_{slash}_32K_XN_{slash}_ADC1_CH5_{slash}_TOUCH8_{slash}_RTC_GPIO8-Pad13)") (class "Default")
      (node (ref "DD1") (pin "13") (pinfunction "IO33_/_32K_XN_/_ADC1_CH5_/_TOUCH8_/_RTC_GPIO8_13") (pintype "passive"))
    )
    (net (code "61") (name "unconnected-(DD1D-SENSOR_CAPN_{slash}_GPIO38_{slash}_ADC1_CH2_{slash}_ADC_PRE_AMP_{slash}_RTC_GPIO2-Pad7)") (class "Default")
      (node (ref "DD1") (pin "7") (pinfunction "SENSOR_CAPN_/_GPIO38_/_ADC1_CH2_/_ADC_PRE_AMP_/_RTC_GPIO2_7") (pintype "input+no_connect"))
    )
    (net (code "62") (name "unconnected-(DD1D-SENSOR_CAPP_{slash}_GPIO37_{slash}_ADC_PRE_AMP_{slash}_ADC1_CH1_{slash}_RTC_GPIO1-Pad6)") (class "Default")
      (node (ref "DD1") (pin "6") (pinfunction "SENSOR_CAPP_/_GPIO37_/_ADC_PRE_AMP_/_ADC1_CH1_/_RTC_GPIO1_6") (pintype "input+no_connect"))
    )
    (net (code "63") (name "unconnected-(DD1D-SENSOR_VN_{slash}_GPIO39_{slash}_ADC1_CH3_{slash}_ADC_PRE_AMP_{slash}_RTC_GPIO3-Pad8)") (class "Default")
      (node (ref "DD1") (pin "8") (pinfunction "SENSOR_VN_/_GPIO39_/_ADC1_CH3_/_ADC_PRE_AMP_/_RTC_GPIO3_8") (pintype "input+no_connect"))
    )
    (net (code "64") (name "unconnected-(DD1D-SENSOR_VP_{slash}_GPIO36_{slash}_ADC_PRE_AMP_{slash}_ADC1_CH0_{slash}_RTC_GPIO0-Pad5)") (class "Default")
      (node (ref "DD1") (pin "5") (pinfunction "SENSOR_VP_/_GPIO36_/_ADC_PRE_AMP_/_ADC1_CH0_/_RTC_GPIO0_5") (pintype "input+no_connect"))
    )
    (net (code "65") (name "unconnected-(DD1F-IO21_{slash}_GPIO21_{slash}_VSPIHD_{slash}_EMAC_TX_EN-Pad42)") (class "Default")
      (node (ref "DD1") (pin "42") (pinfunction "IO21_/_GPIO21_/_VSPIHD_/_EMAC_TX_EN_42") (pintype "passive"))
    )
    (net (code "66") (name "unconnected-(DD1F-IO25_{slash}_GPIO25_{slash}_DAC_1_{slash}_ADC2_CH8_{slash}_RTC_GPIO6_{slash}_EMAC_RXD0-Pad14)") (class "Default")
      (node (ref "DD1") (pin "14") (pinfunction "IO25_/_GPIO25_/_DAC_1_/_ADC2_CH8_/_RTC_GPIO6_/_EMAC_RXD0_14") (pintype "passive"))
    )
    (net (code "67") (name "unconnected-(DD1F-IO26_{slash}_GPIO26_{slash}_DAC_2_{slash}_ADC2_CH9_{slash}_RTC_GPIO7_{slash}_EMAC_RXD1-Pad15)") (class "Default")
      (node (ref "DD1") (pin "15") (pinfunction "IO26_/_GPIO26_/_DAC_2_/_ADC2_CH9_/_RTC_GPIO7_/_EMAC_RXD1_15") (pintype "passive"))
    )
    (net (code "68") (name "unconnected-(DD1F-IO27_{slash}_GPIO27_{slash}_ADC2_CH7_{slash}_TOUCH7_{slash}_RTC_GPIO17_{slash}_EMAC_RX_DV-Pad16)") (class "Default")
      (node (ref "DD1") (pin "16") (pinfunction "IO27_/_GPIO27_/_ADC2_CH7_/_TOUCH7_/_RTC_GPIO17_/_EMAC_RX_DV_16") (pintype "passive"))
    )
    (net (code "69") (name "unconnected-(DD2-CST-Pad23)") (class "Default")
      (node (ref "DD2") (pin "23") (pinfunction "CST_23") (pintype "passive+no_connect"))
    )
    (net (code "70") (name "unconnected-(DD2-DCD-Pad1)") (class "Default")
      (node (ref "DD2") (pin "1") (pinfunction "DCD_1") (pintype "passive+no_connect"))
    )
    (net (code "71") (name "unconnected-(DD2-DSR-Pad27)") (class "Default")
      (node (ref "DD2") (pin "27") (pinfunction "DSR_27") (pintype "passive+no_connect"))
    )
    (net (code "72") (name "unconnected-(DD2-RI-Pad2)") (class "Default")
      (node (ref "DD2") (pin "2") (pinfunction "RI_2") (pintype "passive+no_connect"))
    )
    (net (code "73") (name "unconnected-(DD2-SUSPEND-Pad12)") (class "Default")
      (node (ref "DD2") (pin "12") (pinfunction "SUSPEND_12") (pintype "passive+no_connect"))
    )
    (net (code "74") (name "unconnected-(X1-Pad4)") (class "Default")
      (node (ref "X1") (pin "4") (pinfunction "4_4") (pintype "passive"))
    )
    (net (code "75") (name "unconnected-(X1-Pad6)") (class "Default")
      (node (ref "X1") (pin "6") (pinfunction "6_6") (pintype "passive"))
    )
    (net (code "76") (name "unconnected-(X1-Pad7)") (class "Default")
      (node (ref "X1") (pin "7") (pinfunction "7_7") (pintype "passive"))
    )
    (net (code "77") (name "unconnected-(X1-Pad8)") (class "Default")
      (node (ref "X1") (pin "8") (pinfunction "8_8") (pintype "passive"))
    )
    (net (code "78") (name "unconnected-(X1-Pad9)") (class "Default")
      (node (ref "X1") (pin "9") (pinfunction "9_9") (pintype "passive"))
    )
    (net (code "79") (name "unconnected-(X1-Pad10)") (class "Default")
      (node (ref "X1") (pin "10") (pinfunction "10_10") (pintype "passive"))
    )
    (net (code "80") (name "unconnected-(X1-Pad11)") (class "Default")
      (node (ref "X1") (pin "11") (pinfunction "11_11") (pintype "passive"))
    )
  )
)
